# Sheet1.net
KiCad netlist of a schematic drawn in Altium Designer
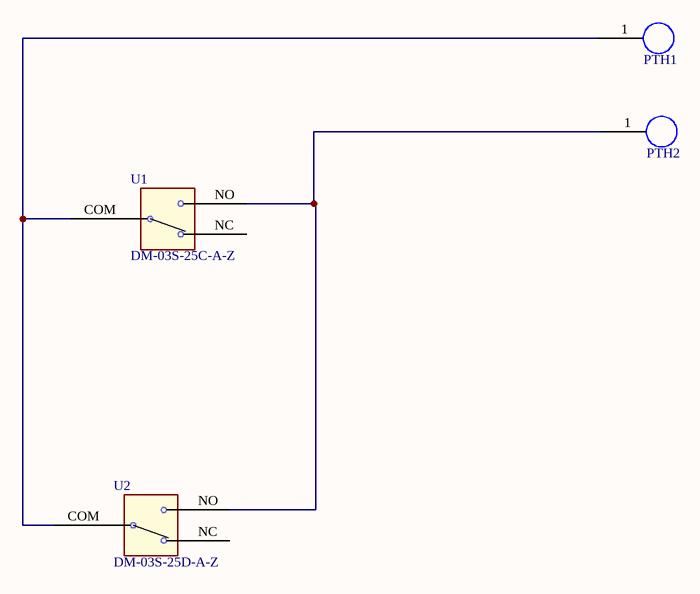
[diagram p0: Sheet1.SchDoc]

(export (version "E")
  (design (tool "Eeschema 10.0.6"))
  (components
    (comp (ref "PTH1")
      (value "Plated through hole")
      (footprint "PTH_70mil")
      (description "Plated Through Hole")
      (libsource (lib "PTH_70mil") (part "PTH"))
    )
    (comp (ref "PTH2")
      (value "Plated through hole")
      (footprint "PTH_70mil")
      (description "Plated Through Hole")
      (libsource (lib "PTH_70mil") (part "PTH"))
    )
    (comp (ref "U1")
      (value "DM-03S-25C-A-Z")
      (footprint "DM-03S-25C-A-Z")
      (description "Roller switch left")
      (libsource (lib "DM-03S-25D-A-Z") (part "Component_1"))
    )
    (comp (ref "U2")
      (value "DM-03S-25D-A-Z")
      (footprint "DM-03S-25D-A-Z")
      (description "Roller switch right")
      (libsource (lib "DM-03S-25C-A-Z") (part "Component_1"))
    )
  )
  (nets
    (net (code "1") (name "Net-(PTH1-PTH)") (class "Default")
      (node (ref "PTH1") (pin "1") (pinfunction "PTH_1") (pintype "passive"))
      (node (ref "U1") (pin "COM") (pinfunction "COM_COM") (pintype "passive"))
      (node (ref "U2") (pin "COM") (pinfunction "COM_COM") (pintype "passive"))
    )
    (net (code "2") (name "Net-(PTH2-PTH)") (class "Default")
      (node (ref "PTH2") (pin "1") (pinfunction "PTH_1") (pintype "passive"))
      (node (ref "U1") (pin "NO") (pinfunction "NO_NO") (pintype "passive"))
      (node (ref "U2") (pin "NO") (pinfunction "NO_NO") (pintype "passive"))
    )
    (net (code "3") (name "unconnected-(U1-PadNC)") (class "Default")
      (node (ref "U1") (pin "NC") (pinfunction "NC_NC") (pintype "passive"))
    )
    (net (code "4") (name "unconnected-(U2-PadNC)") (class "Default")
      (node (ref "U2") (pin "NC") (pinfunction "NC_NC") (pintype "passive"))
    )
  )
)
